# 74hc595.net
KiCad netlist of a schematic drawn in Altium Designer
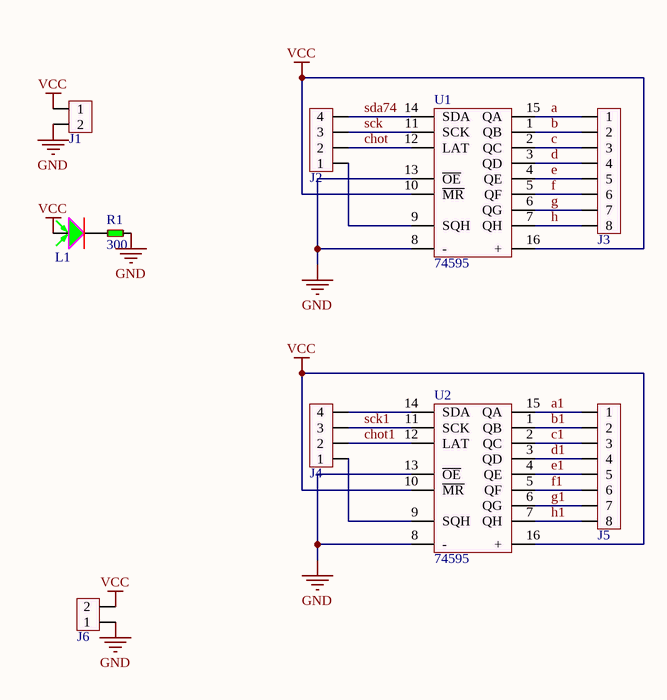
[diagram p0: 74hc595.SchDoc]

(export (version "E")
  (design (tool "Eeschema 10.0.6"))
  (components
    (comp (ref "J1")
      (value "JP2")
      (footprint "JP2-D1T")
      (description "WR-PHD 2.54 mm Angled Socket Header")
      (libsource (lib "Integrated_Library") (part "JP2"))
    )
    (comp (ref "J2")
      (value "JP4")
      (footprint "JP4-C1T")
      (description "WR-PHD 2.54 mm Angled Socket Header")
      (libsource (lib "Integrated_Library") (part "JP4"))
    )
    (comp (ref "J3")
      (value "JP8")
      (footprint "JP8-D1T")
      (description "WR-PHD 2.54 mm Angled Socket Header")
      (libsource (lib "Integrated_Library") (part "JP8"))
    )
    (comp (ref "J4")
      (value "JP4")
      (footprint "JP4-C1T")
      (description "WR-PHD 2.54 mm Angled Socket Header")
      (libsource (lib "Integrated_Library") (part "JP4"))
    )
    (comp (ref "J5")
      (value "JP8")
      (footprint "JP8-D1T")
      (description "WR-PHD 2.54 mm Angled Socket Header")
      (libsource (lib "Integrated_Library") (part "JP8"))
    )
    (comp (ref "J6")
      (value "JP2")
      (footprint "JP2-D1T")
      (description "WR-PHD 2.54 mm Angled Socket Header")
      (libsource (lib "") (part "JP2_1"))
    )
    (comp (ref "L1")
      (value "LED SMD")
      (footprint "L0805R")
      (description "LED DIFFUSED 1206 SMD")
      (libsource (lib "Integrated_Library") (part "LED SMD"))
    )
    (comp (ref "R1")
      (value "300")
      (footprint "R0805")
      (description "RES SMD 0.0 OHM JUMPER 1/8W 0805")
      (libsource (lib "Integrated_Library") (part "Res-SMD"))
    )
    (comp (ref "U1")
      (value "74595")
      (footprint "SO16A")
      (libsource (lib "Integrated_Library") (part "74595"))
    )
    (comp (ref "U2")
      (value "74595")
      (footprint "SO16A")
      (libsource (lib "Integrated_Library") (part "74595"))
    )
  )
  (nets
    (net (code "1") (name "/a") (class "Default")
      (node (ref "J3") (pin "1") (pinfunction "1_1") (pintype "passive"))
      (node (ref "U1") (pin "15") (pinfunction "QA_15") (pintype "passive"))
    )
    (net (code "2") (name "/a1") (class "Default")
      (node (ref "J5") (pin "1") (pinfunction "1_1") (pintype "passive"))
      (node (ref "U2") (pin "15") (pinfunction "QA_15") (pintype "passive"))
    )
    (net (code "3") (name "/b") (class "Default")
      (node (ref "J3") (pin "2") (pinfunction "2_2") (pintype "passive"))
      (node (ref "U1") (pin "1") (pinfunction "QB_1") (pintype "passive"))
    )
    (net (code "4") (name "/b1") (class "Default")
      (node (ref "J5") (pin "2") (pinfunction "2_2") (pintype "passive"))
      (node (ref "U2") (pin "1") (pinfunction "QB_1") (pintype "passive"))
    )
    (net (code "5") (name "/c") (class "Default")
      (node (ref "J3") (pin "3") (pinfunction "3_3") (pintype "passive"))
      (node (ref "U1") (pin "2") (pinfunction "QC_2") (pintype "passive"))
    )
    (net (code "6") (name "/c1") (class "Default")
      (node (ref "J5") (pin "3") (pinfunction "3_3") (pintype "passive"))
      (node (ref "U2") (pin "2") (pinfunction "QC_2") (pintype "passive"))
    )
    (net (code "7") (name "/chot") (class "Default")
      (node (ref "J2") (pin "2") (pinfunction "2_2") (pintype "passive"))
      (node (ref "U1") (pin "12") (pinfunction "LAT_12") (pintype "passive"))
    )
    (net (code "8") (name "/chot1") (class "Default")
      (node (ref "J4") (pin "2") (pinfunction "2_2") (pintype "passive"))
      (node (ref "U2") (pin "12") (pinfunction "LAT_12") (pintype "passive"))
    )
    (net (code "9") (name "/d") (class "Default")
      (node (ref "J3") (pin "4") (pinfunction "4_4") (pintype "passive"))
      (node (ref "U1") (pin "3") (pinfunction "QD_3") (pintype "passive"))
    )
    (net (code "10") (name "/d1") (class "Default")
      (node (ref "J5") (pin "4") (pinfunction "4_4") (pintype "passive"))
      (node (ref "U2") (pin "3") (pinfunction "QD_3") (pintype "passive"))
    )
    (net (code "11") (name "/e") (class "Default")
      (node (ref "J3") (pin "5") (pinfunction "5_5") (pintype "passive"))
      (node (ref "U1") (pin "4") (pinfunction "QE_4") (pintype "passive"))
    )
    (net (code "12") (name "/e1") (class "Default")
      (node (ref "J5") (pin "5") (pinfunction "5_5") (pintype "passive"))
      (node (ref "U2") (pin "4") (pinfunction "QE_4") (pintype "passive"))
    )
    (net (code "13") (name "/f") (class "Default")
      (node (ref "J3") (pin "6") (pinfunction "6_6") (pintype "passive"))
      (node (ref "U1") (pin "5") (pinfunction "QF_5") (pintype "passive"))
    )
    (net (code "14") (name "/f1") (class "Default")
      (node (ref "J5") (pin "6") (pinfunction "6_6") (pintype "passive"))
      (node (ref "U2") (pin "5") (pinfunction "QF_5") (pintype "passive"))
    )
    (net (code "15") (name "/g") (class "Default")
      (node (ref "J3") (pin "7") (pinfunction "7_7") (pintype "passive"))
      (node (ref "U1") (pin "6") (pinfunction "QG_6") (pintype "passive"))
    )
    (net (code "16") (name "/g1") (class "Default")
      (node (ref "J5") (pin "7") (pinfunction "7_7") (pintype "passive"))
      (node (ref "U2") (pin "6") (pinfunction "QG_6") (pintype "passive"))
    )
    (net (code "17") (name "/h") (class "Default")
      (node (ref "J3") (pin "8") (pinfunction "8_8") (pintype "passive"))
      (node (ref "U1") (pin "7") (pinfunction "QH_7") (pintype "passive"))
    )
    (net (code "18") (name "/h1") (class "Default")
      (node (ref "J5") (pin "8") (pinfunction "8_8") (pintype "passive"))
      (node (ref "U2") (pin "7") (pinfunction "QH_7") (pintype "passive"))
    )
    (net (code "19") (name "/sck") (class "Default")
      (node (ref "J2") (pin "3") (pinfunction "3_3") (pintype "passive"))
      (node (ref "U1") (pin "11") (pinfunction "SCK_11") (pintype "passive"))
    )
    (net (code "20") (name "/sck1") (class "Default")
      (node (ref "J4") (pin "3") (pinfunction "3_3") (pintype "passive"))
      (node (ref "U2") (pin "11") (pinfunction "SCK_11") (pintype "passive"))
    )
    (net (code "21") (name "/sda74") (class "Default")
      (node (ref "J2") (pin "4") (pinfunction "4_4") (pintype "passive"))
      (node (ref "U1") (pin "14") (pinfunction "SDA_14") (pintype "passive"))
    )
    (net (code "22") (name "GND") (class "Default")
      (node (ref "J1") (pin "2") (pinfunction "2_2") (pintype "passive"))
      (node (ref "J6") (pin "1") (pinfunction "1_1") (pintype "passive"))
      (node (ref "R1") (pin "1") (pinfunction "1_1") (pintype "passive"))
      (node (ref "U1") (pin "13") (pinfunction "~{OE}_13") (pintype "passive"))
      (node (ref "U1") (pin "8") (pinfunction "-_8") (pintype "passive"))
      (node (ref "U2") (pin "13") (pinfunction "~{OE}_13") (pintype "passive"))
      (node (ref "U2") (pin "8") (pinfunction "-_8") (pintype "passive"))
    )
    (net (code "23") (name "Net-(L1-K)") (class "Default")
      (node (ref "L1") (pin "2") (pinfunction "K_2") (pintype "passive"))
      (node (ref "R1") (pin "2") (pinfunction "2_2") (pintype "passive"))
    )
    (net (code "24") (name "Net-(U1-SQH)") (class "Default")
      (node (ref "J2") (pin "1") (pinfunction "1_1") (pintype "passive"))
      (node (ref "U1") (pin "9") (pinfunction "SQH_9") (pintype "passive"))
    )
    (net (code "25") (name "Net-(U2-SDA)") (class "Default")
      (node (ref "J4") (pin "4") (pinfunction "4_4") (pintype "passive"))
      (node (ref "U2") (pin "14") (pinfunction "SDA_14") (pintype "passive"))
    )
    (net (code "26") (name "Net-(U2-SQH)") (class "Default")
      (node (ref "J4") (pin "1") (pinfunction "1_1") (pintype "passive"))
      (node (ref "U2") (pin "9") (pinfunction "SQH_9") (pintype "passive"))
    )
    (net (code "27") (name "VCC") (class "Default")
      (node (ref "J1") (pin "1") (pinfunction "1_1") (pintype "passive"))
      (node (ref "J6") (pin "2") (pinfunction "2_2") (pintype "passive"))
      (node (ref "L1") (pin "1") (pinfunction "A_1") (pintype "passive"))
      (node (ref "U1") (pin "10") (pinfunction "~{MR}_10") (pintype "passive"))
      (node (ref "U1") (pin "16") (pinfunction "+_16") (pintype "passive"))
      (node (ref "U2") (pin "10") (pinfunction "~{MR}_10") (pintype "passive"))
      (node (ref "U2") (pin "16") (pinfunction "+_16") (pintype "passive"))
    )
  )
)
